# DIO.net
KiCad netlist of a schematic drawn in Altium Designer
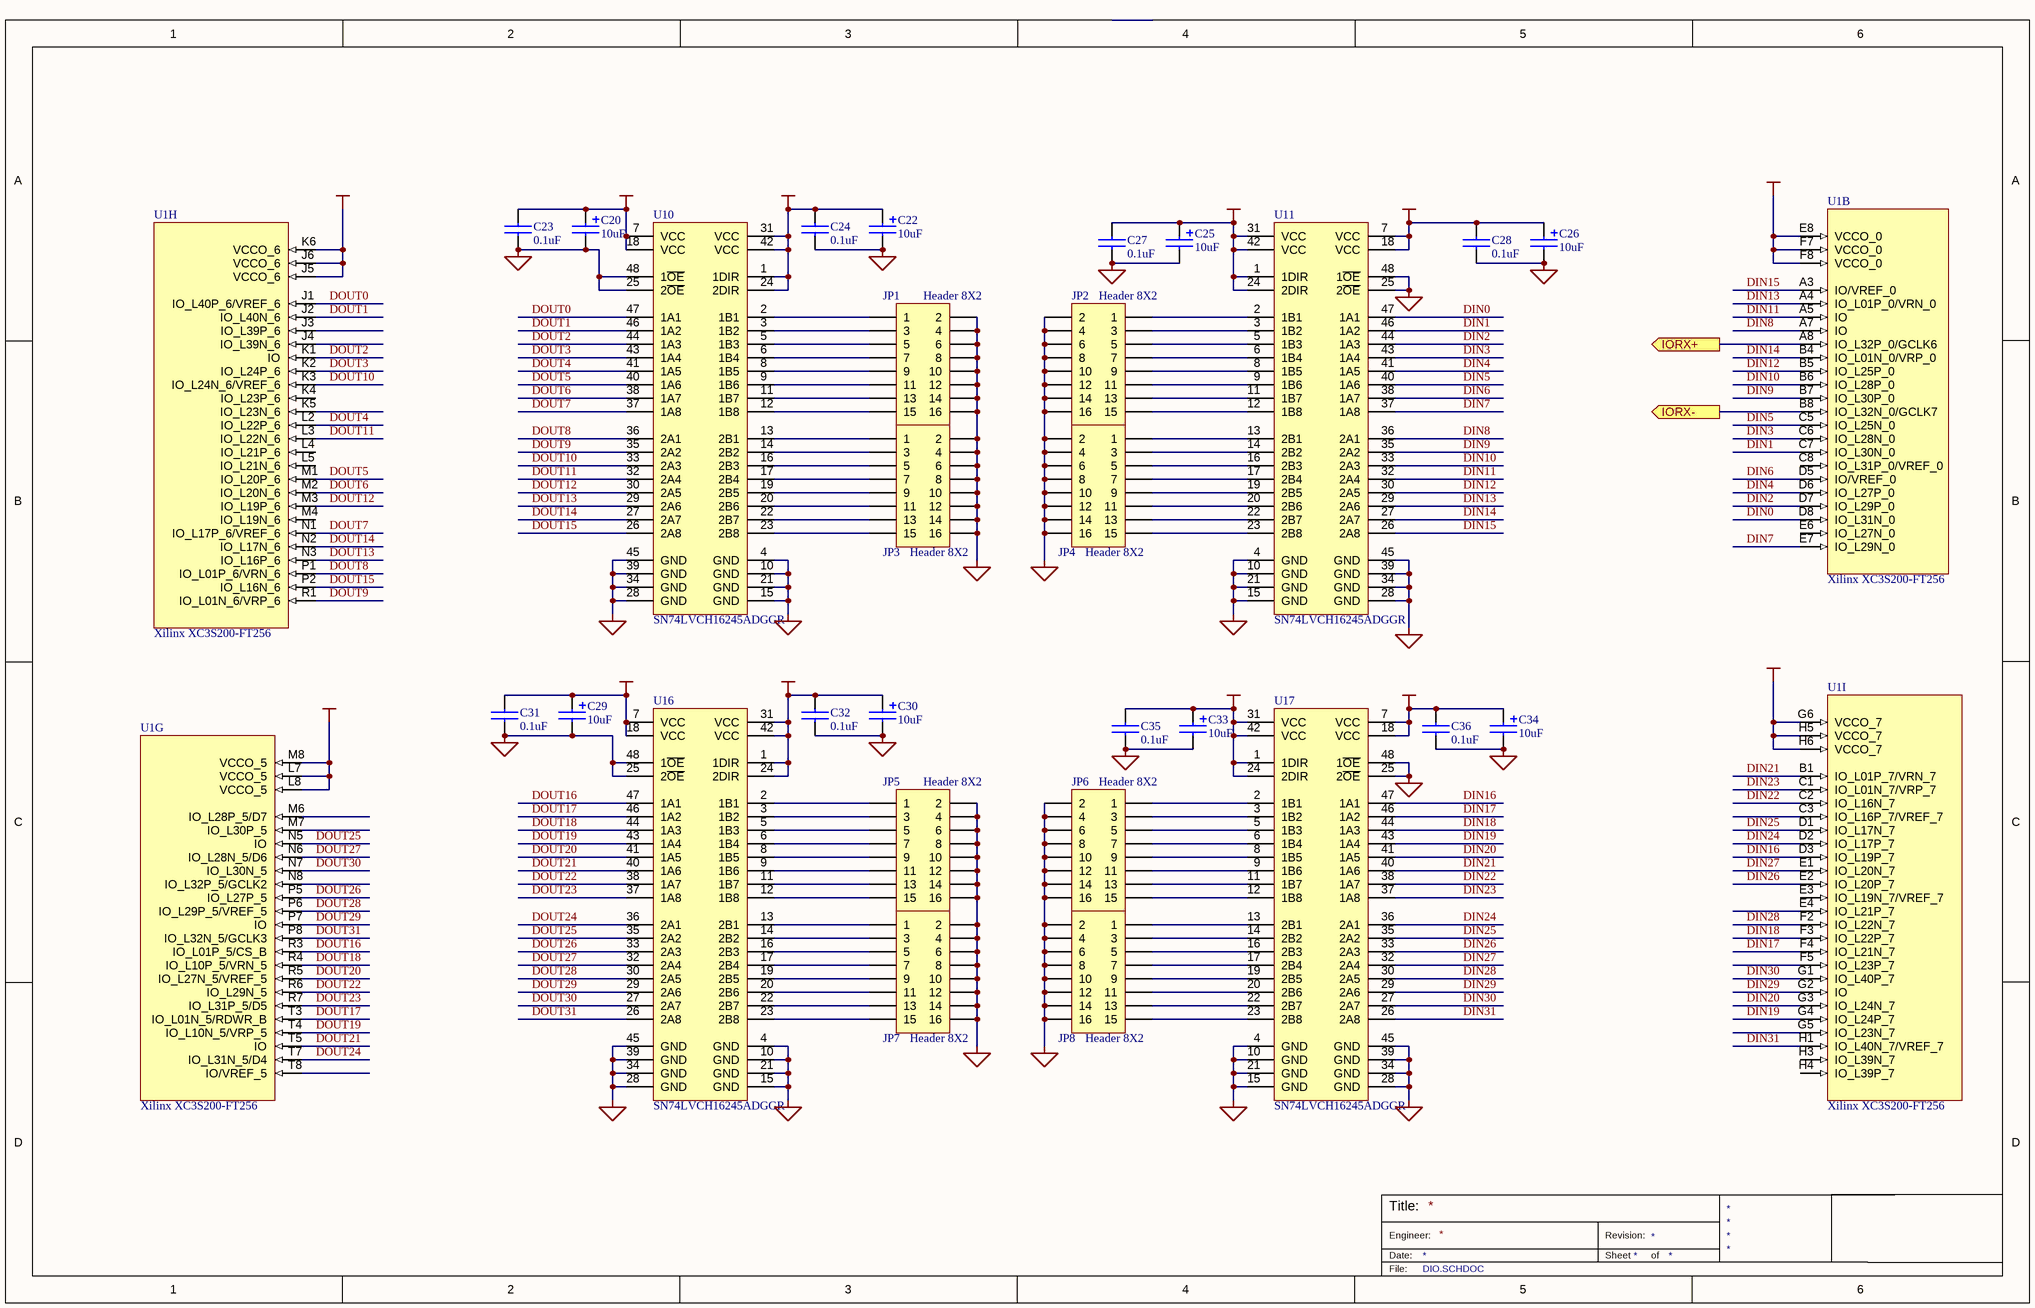
[diagram p0: DIO.SCHDOC]

(export (version "E")
  (design (tool "Eeschema 10.0.6"))
  (components
    (comp (ref "C20")
      (value "10uF")
      (footprint "3216")
      (description "Standard Capacitor")
      (fields (field (name "Comment") "POLCAP"))
      (libsource (lib "parts") (part "POLCAP"))
    )
    (comp (ref "C22")
      (value "10uF")
      (footprint "3216")
      (description "Standard Capacitor")
      (fields (field (name "Comment") "POLCAP"))
      (libsource (lib "parts") (part "POLCAP"))
    )
    (comp (ref "C23")
      (value "0.1uF")
      (footprint "0603")
      (description "Standard Capacitor")
      (fields (field (name "Comment") "CAPACITOR"))
      (libsource (lib "parts") (part "CAPACITOR"))
    )
    (comp (ref "C24")
      (value "0.1uF")
      (footprint "0603")
      (description "Standard Capacitor")
      (fields (field (name "Comment") "CAPACITOR"))
      (libsource (lib "parts") (part "CAPACITOR"))
    )
    (comp (ref "C25")
      (value "10uF")
      (footprint "3216")
      (description "Standard Capacitor")
      (fields (field (name "Comment") "POLCAP"))
      (libsource (lib "parts") (part "POLCAP"))
    )
    (comp (ref "C26")
      (value "10uF")
      (footprint "3216")
      (description "Standard Capacitor")
      (fields (field (name "Comment") "POLCAP"))
      (libsource (lib "parts") (part "POLCAP"))
    )
    (comp (ref "C27")
      (value "0.1uF")
      (footprint "0603")
      (description "Standard Capacitor")
      (fields (field (name "Comment") "CAPACITOR"))
      (libsource (lib "parts") (part "CAPACITOR"))
    )
    (comp (ref "C28")
      (value "0.1uF")
      (footprint "0603")
      (description "Standard Capacitor")
      (fields (field (name "Comment") "CAPACITOR"))
      (libsource (lib "parts") (part "CAPACITOR"))
    )
    (comp (ref "C29")
      (value "10uF")
      (footprint "3216")
      (description "Standard Capacitor")
      (fields (field (name "Comment") "POLCAP"))
      (libsource (lib "parts") (part "POLCAP"))
    )
    (comp (ref "C30")
      (value "10uF")
      (footprint "3216")
      (description "Standard Capacitor")
      (fields (field (name "Comment") "POLCAP"))
      (libsource (lib "parts") (part "POLCAP"))
    )
    (comp (ref "C31")
      (value "0.1uF")
      (footprint "0603")
      (description "Standard Capacitor")
      (fields (field (name "Comment") "CAPACITOR"))
      (libsource (lib "parts") (part "CAPACITOR"))
    )
    (comp (ref "C32")
      (value "0.1uF")
      (footprint "0603")
      (description "Standard Capacitor")
      (fields (field (name "Comment") "CAPACITOR"))
      (libsource (lib "parts") (part "CAPACITOR"))
    )
    (comp (ref "C33")
      (value "10uF")
      (footprint "3216")
      (description "Standard Capacitor")
      (fields (field (name "Comment") "POLCAP"))
      (libsource (lib "parts") (part "POLCAP"))
    )
    (comp (ref "C34")
      (value "10uF")
      (footprint "3216")
      (description "Standard Capacitor")
      (fields (field (name "Comment") "POLCAP"))
      (libsource (lib "parts") (part "POLCAP"))
    )
    (comp (ref "C35")
      (value "0.1uF")
      (footprint "0603")
      (description "Standard Capacitor")
      (fields (field (name "Comment") "CAPACITOR"))
      (libsource (lib "parts") (part "CAPACITOR"))
    )
    (comp (ref "C36")
      (value "0.1uF")
      (footprint "0603")
      (description "Standard Capacitor")
      (fields (field (name "Comment") "CAPACITOR"))
      (libsource (lib "parts") (part "CAPACITOR"))
    )
    (comp (ref "JP1")
      (value "Header 8X2")
      (footprint "HDR2X8")
      (description "Header, 8-Pin, Dual row")
      (fields (field (name "MANUFACTURER") "Generic Components") (field (name "PUBLISHER") "Altium Limited"))
      (libsource (lib "") (part "Header 8X2_1"))
    )
    (comp (ref "JP2")
      (value "Header 8X2")
      (footprint "HDR2X8")
      (description "Header, 8-Pin, Dual row")
      (fields (field (name "MANUFACTURER") "Generic Components") (field (name "PUBLISHER") "Altium Limited"))
      (libsource (lib "Miscellaneous Connectors") (part "Header 8X2"))
    )
    (comp (ref "JP3")
      (value "Header 8X2")
      (footprint "HDR2X8")
      (description "Header, 8-Pin, Dual row")
      (fields (field (name "MANUFACTURER") "Generic Components") (field (name "PUBLISHER") "Altium Limited"))
      (libsource (lib "") (part "Header 8X2_1"))
    )
    (comp (ref "JP4")
      (value "Header 8X2")
      (footprint "HDR2X8")
      (description "Header, 8-Pin, Dual row")
      (fields (field (name "MANUFACTURER") "Generic Components") (field (name "PUBLISHER") "Altium Limited"))
      (libsource (lib "Miscellaneous Connectors") (part "Header 8X2"))
    )
    (comp (ref "JP5")
      (value "Header 8X2")
      (footprint "HDR2X8")
      (description "Header, 8-Pin, Dual row")
      (fields (field (name "MANUFACTURER") "Generic Components") (field (name "PUBLISHER") "Altium Limited"))
      (libsource (lib "") (part "Header 8X2_1"))
    )
    (comp (ref "JP6")
      (value "Header 8X2")
      (footprint "HDR2X8")
      (description "Header, 8-Pin, Dual row")
      (fields (field (name "MANUFACTURER") "Generic Components") (field (name "PUBLISHER") "Altium Limited"))
      (libsource (lib "Miscellaneous Connectors") (part "Header 8X2"))
    )
    (comp (ref "JP7")
      (value "Header 8X2")
      (footprint "HDR2X8")
      (description "Header, 8-Pin, Dual row")
      (fields (field (name "MANUFACTURER") "Generic Components") (field (name "PUBLISHER") "Altium Limited"))
      (libsource (lib "") (part "Header 8X2_1"))
    )
    (comp (ref "JP8")
      (value "Header 8X2")
      (footprint "HDR2X8")
      (description "Header, 8-Pin, Dual row")
      (fields (field (name "MANUFACTURER") "Generic Components") (field (name "PUBLISHER") "Altium Limited"))
      (libsource (lib "Miscellaneous Connectors") (part "Header 8X2"))
    )
    (comp (ref "U1")
      (value "Xilinx XC3S200-FT256")
      (footprint "Xilinx FT256 BGA")
      (description "Xilinx Spartan-3 FPGA")
      (libsource (lib "") (part "XC3S200-FT256_1"))
    )
    (comp (ref "U10")
      (value "SN74LVCH16245ADGGR")
      (footprint "TSSO12x8-G48/X.3")
      (description "16-bit bus transceiver with 3-state outputs")
      (libsource (lib "") (part "SN74LVCH16245ADGGR_1"))
    )
    (comp (ref "U11")
      (value "SN74LVCH16245ADGGR")
      (footprint "TSSO12x8-G48/X.3")
      (description "16-bit bus transceiver with 3-state outputs")
      (libsource (lib "parts") (part "SN74LVCH16245ADGGR"))
    )
    (comp (ref "U16")
      (value "SN74LVCH16245ADGGR")
      (footprint "TSSO12x8-G48/X.3")
      (description "16-bit bus transceiver with 3-state outputs")
      (libsource (lib "") (part "SN74LVCH16245ADGGR_1"))
    )
    (comp (ref "U17")
      (value "SN74LVCH16245ADGGR")
      (footprint "TSSO12x8-G48/X.3")
      (description "16-bit bus transceiver with 3-state outputs")
      (libsource (lib "parts") (part "SN74LVCH16245ADGGR"))
    )
  )
  (nets
    (net (code "1") (name "+2.5VCC") (class "Default")
      (node (ref "C22") (pin "1") (pintype "passive"))
      (node (ref "C24") (pin "1") (pintype "passive"))
      (node (ref "C25") (pin "1") (pintype "passive"))
      (node (ref "C27") (pin "1") (pintype "passive"))
      (node (ref "C30") (pin "1") (pintype "passive"))
      (node (ref "C32") (pin "1") (pintype "passive"))
      (node (ref "C33") (pin "1") (pintype "passive"))
      (node (ref "C35") (pin "1") (pintype "passive"))
      (node (ref "U1") (pin "E8") (pinfunction "VCCO_0_E8") (pintype "input"))
      (node (ref "U1") (pin "F7") (pinfunction "VCCO_0_F7") (pintype "input"))
      (node (ref "U1") (pin "F8") (pinfunction "VCCO_0_F8") (pintype "input"))
      (node (ref "U1") (pin "G6") (pinfunction "VCCO_7_G6") (pintype "input"))
      (node (ref "U1") (pin "H5") (pinfunction "VCCO_7_H5") (pintype "input"))
      (node (ref "U1") (pin "H6") (pinfunction "VCCO_7_H6") (pintype "input"))
      (node (ref "U1") (pin "J5") (pinfunction "VCCO_6_J5") (pintype "input"))
      (node (ref "U1") (pin "J6") (pinfunction "VCCO_6_J6") (pintype "input"))
      (node (ref "U1") (pin "K6") (pinfunction "VCCO_6_K6") (pintype "input"))
      (node (ref "U1") (pin "L7") (pinfunction "VCCO_5_L7") (pintype "input"))
      (node (ref "U1") (pin "L8") (pinfunction "VCCO_5_L8") (pintype "input"))
      (node (ref "U1") (pin "M8") (pinfunction "VCCO_5_M8") (pintype "input"))
      (node (ref "U10") (pin "1") (pinfunction "1DIR_1") (pintype "passive"))
      (node (ref "U10") (pin "24") (pinfunction "2DIR_24") (pintype "passive"))
      (node (ref "U10") (pin "31") (pinfunction "VCC_31") (pintype "power_in"))
      (node (ref "U10") (pin "42") (pinfunction "VCC_42") (pintype "power_in"))
      (node (ref "U11") (pin "1") (pinfunction "1DIR_1") (pintype "passive"))
      (node (ref "U11") (pin "24") (pinfunction "2DIR_24") (pintype "passive"))
      (node (ref "U11") (pin "31") (pinfunction "VCC_31") (pintype "power_in"))
      (node (ref "U11") (pin "42") (pinfunction "VCC_42") (pintype "power_in"))
      (node (ref "U16") (pin "1") (pinfunction "1DIR_1") (pintype "passive"))
      (node (ref "U16") (pin "24") (pinfunction "2DIR_24") (pintype "passive"))
      (node (ref "U16") (pin "31") (pinfunction "VCC_31") (pintype "power_in"))
      (node (ref "U16") (pin "42") (pinfunction "VCC_42") (pintype "power_in"))
      (node (ref "U17") (pin "1") (pinfunction "1DIR_1") (pintype "passive"))
      (node (ref "U17") (pin "24") (pinfunction "2DIR_24") (pintype "passive"))
      (node (ref "U17") (pin "31") (pinfunction "VCC_31") (pintype "power_in"))
      (node (ref "U17") (pin "42") (pinfunction "VCC_42") (pintype "power_in"))
    )
    (net (code "2") (name "+5VCC") (class "Default")
      (node (ref "C20") (pin "1") (pintype "passive"))
      (node (ref "C23") (pin "1") (pintype "passive"))
      (node (ref "C26") (pin "1") (pintype "passive"))
      (node (ref "C28") (pin "1") (pintype "passive"))
      (node (ref "C29") (pin "1") (pintype "passive"))
      (node (ref "C31") (pin "1") (pintype "passive"))
      (node (ref "C34") (pin "1") (pintype "passive"))
      (node (ref "C36") (pin "1") (pintype "passive"))
      (node (ref "U10") (pin "18") (pinfunction "VCC_18") (pintype "power_in"))
      (node (ref "U10") (pin "7") (pinfunction "VCC_7") (pintype "power_in"))
      (node (ref "U11") (pin "18") (pinfunction "VCC_18") (pintype "power_in"))
      (node (ref "U11") (pin "7") (pinfunction "VCC_7") (pintype "power_in"))
      (node (ref "U16") (pin "18") (pinfunction "VCC_18") (pintype "power_in"))
      (node (ref "U16") (pin "7") (pinfunction "VCC_7") (pintype "power_in"))
      (node (ref "U17") (pin "18") (pinfunction "VCC_18") (pintype "power_in"))
      (node (ref "U17") (pin "7") (pinfunction "VCC_7") (pintype "power_in"))
    )
    (net (code "3") (name "/DIN0") (class "Default")
      (node (ref "U1") (pin "D8") (pinfunction "IO_L31N_0_D8") (pintype "input"))
      (node (ref "U11") (pin "47") (pinfunction "1A1_47") (pintype "passive"))
    )
    (net (code "4") (name "/DIN1") (class "Default")
      (node (ref "U1") (pin "C7") (pinfunction "IO_L30N_0_C7") (pintype "input"))
      (node (ref "U11") (pin "46") (pinfunction "1A2_46") (pintype "passive"))
    )
    (net (code "5") (name "/DIN2") (class "Default")
      (node (ref "U1") (pin "D7") (pinfunction "IO_L29P_0_D7") (pintype "input"))
      (node (ref "U11") (pin "44") (pinfunction "1A3_44") (pintype "passive"))
    )
    (net (code "6") (name "/DIN3") (class "Default")
      (node (ref "U1") (pin "C6") (pinfunction "IO_L28N_0_C6") (pintype "input"))
      (node (ref "U11") (pin "43") (pinfunction "1A4_43") (pintype "passive"))
    )
    (net (code "7") (name "/DIN4") (class "Default")
      (node (ref "U1") (pin "D6") (pinfunction "IO_L27P_0_D6") (pintype "input"))
      (node (ref "U11") (pin "41") (pinfunction "1A5_41") (pintype "passive"))
    )
    (net (code "8") (name "/DIN5") (class "Default")
      (node (ref "U1") (pin "C5") (pinfunction "IO_L25N_0_C5") (pintype "input"))
      (node (ref "U11") (pin "40") (pinfunction "1A6_40") (pintype "passive"))
    )
    (net (code "9") (name "/DIN6") (class "Default")
      (node (ref "U1") (pin "D5") (pinfunction "IO/VREF_0_D5") (pintype "input"))
      (node (ref "U11") (pin "38") (pinfunction "1A7_38") (pintype "passive"))
    )
    (net (code "10") (name "/DIN7") (class "Default")
      (node (ref "U1") (pin "E7") (pinfunction "IO_L29N_0_E7") (pintype "input"))
      (node (ref "U11") (pin "37") (pinfunction "1A8_37") (pintype "passive"))
    )
    (net (code "11") (name "/DIN8") (class "Default")
      (node (ref "U1") (pin "A7") (pinfunction "IO_A7") (pintype "input"))
      (node (ref "U11") (pin "36") (pinfunction "2A1_36") (pintype "passive"))
    )
    (net (code "12") (name "/DIN9") (class "Default")
      (node (ref "U1") (pin "B7") (pinfunction "IO_L30P_0_B7") (pintype "input"))
      (node (ref "U11") (pin "35") (pinfunction "2A2_35") (pintype "passive"))
    )
    (net (code "13") (name "/DIN10") (class "Default")
      (node (ref "U1") (pin "B6") (pinfunction "IO_L28P_0_B6") (pintype "input"))
      (node (ref "U11") (pin "33") (pinfunction "2A3_33") (pintype "passive"))
    )
    (net (code "14") (name "/DIN11") (class "Default")
      (node (ref "U1") (pin "A5") (pinfunction "IO_A5") (pintype "input"))
      (node (ref "U11") (pin "32") (pinfunction "2A4_32") (pintype "passive"))
    )
    (net (code "15") (name "/DIN12") (class "Default")
      (node (ref "U1") (pin "B5") (pinfunction "IO_L25P_0_B5") (pintype "input"))
      (node (ref "U11") (pin "30") (pinfunction "2A5_30") (pintype "passive"))
    )
    (net (code "16") (name "/DIN13") (class "Default")
      (node (ref "U1") (pin "A4") (pinfunction "IO_L01P_0/VRN_0_A4") (pintype "input"))
      (node (ref "U11") (pin "29") (pinfunction "2A6_29") (pintype "passive"))
    )
    (net (code "17") (name "/DIN14") (class "Default")
      (node (ref "U1") (pin "B4") (pinfunction "IO_L01N_0/VRP_0_B4") (pintype "input"))
      (node (ref "U11") (pin "27") (pinfunction "2A7_27") (pintype "passive"))
    )
    (net (code "18") (name "/DIN15") (class "Default")
      (node (ref "U1") (pin "A3") (pinfunction "IO/VREF_0_A3") (pintype "input"))
      (node (ref "U11") (pin "26") (pinfunction "2A8_26") (pintype "passive"))
    )
    (net (code "19") (name "/DIN16") (class "Default")
      (node (ref "U1") (pin "D3") (pinfunction "IO_L19P_7_D3") (pintype "input"))
      (node (ref "U17") (pin "47") (pinfunction "1A1_47") (pintype "passive"))
    )
    (net (code "20") (name "/DIN17") (class "Default")
      (node (ref "U1") (pin "F4") (pinfunction "IO_L21N_7_F4") (pintype "input"))
      (node (ref "U17") (pin "46") (pinfunction "1A2_46") (pintype "passive"))
    )
    (net (code "21") (name "/DIN18") (class "Default")
      (node (ref "U1") (pin "F3") (pinfunction "IO_L22P_7_F3") (pintype "input"))
      (node (ref "U17") (pin "44") (pinfunction "1A3_44") (pintype "passive"))
    )
    (net (code "22") (name "/DIN19") (class "Default")
      (node (ref "U1") (pin "G4") (pinfunction "IO_L24P_7_G4") (pintype "input"))
      (node (ref "U17") (pin "43") (pinfunction "1A4_43") (pintype "passive"))
    )
    (net (code "23") (name "/DIN20") (class "Default")
      (node (ref "U1") (pin "G3") (pinfunction "IO_L24N_7_G3") (pintype "input"))
      (node (ref "U17") (pin "41") (pinfunction "1A5_41") (pintype "passive"))
    )
    (net (code "24") (name "/DIN21") (class "Default")
      (node (ref "U1") (pin "B1") (pinfunction "IO_L01P_7/VRN_7_B1") (pintype "input"))
      (node (ref "U17") (pin "40") (pinfunction "1A6_40") (pintype "passive"))
    )
    (net (code "25") (name "/DIN22") (class "Default")
      (node (ref "U1") (pin "C2") (pinfunction "IO_L16N_7_C2") (pintype "input"))
      (node (ref "U17") (pin "38") (pinfunction "1A7_38") (pintype "passive"))
    )
    (net (code "26") (name "/DIN23") (class "Default")
      (node (ref "U1") (pin "C1") (pinfunction "IO_L01N_7/VRP_7_C1") (pintype "input"))
      (node (ref "U17") (pin "37") (pinfunction "1A8_37") (pintype "passive"))
    )
    (net (code "27") (name "/DIN24") (class "Default")
      (node (ref "U1") (pin "D2") (pinfunction "IO_L17P_7_D2") (pintype "input"))
      (node (ref "U17") (pin "36") (pinfunction "2A1_36") (pintype "passive"))
    )
    (net (code "28") (name "/DIN25") (class "Default")
      (node (ref "U1") (pin "D1") (pinfunction "IO_L17N_7_D1") (pintype "input"))
      (node (ref "U17") (pin "35") (pinfunction "2A2_35") (pintype "passive"))
    )
    (net (code "29") (name "/DIN26") (class "Default")
      (node (ref "U1") (pin "E2") (pinfunction "IO_L20P_7_E2") (pintype "input"))
      (node (ref "U17") (pin "33") (pinfunction "2A3_33") (pintype "passive"))
    )
    (net (code "30") (name "/DIN27") (class "Default")
      (node (ref "U1") (pin "E1") (pinfunction "IO_L20N_7_E1") (pintype "input"))
      (node (ref "U17") (pin "32") (pinfunction "2A4_32") (pintype "passive"))
    )
    (net (code "31") (name "/DIN28") (class "Default")
      (node (ref "U1") (pin "F2") (pinfunction "IO_L22N_7_F2") (pintype "input"))
      (node (ref "U17") (pin "30") (pinfunction "2A5_30") (pintype "passive"))
    )
    (net (code "32") (name "/DIN29") (class "Default")
      (node (ref "U1") (pin "G2") (pinfunction "IO_G2") (pintype "input"))
      (node (ref "U17") (pin "29") (pinfunction "2A6_29") (pintype "passive"))
    )
    (net (code "33") (name "/DIN30") (class "Default")
      (node (ref "U1") (pin "G1") (pinfunction "IO_L40P_7_G1") (pintype "input"))
      (node (ref "U17") (pin "27") (pinfunction "2A7_27") (pintype "passive"))
    )
    (net (code "34") (name "/DIN31") (class "Default")
      (node (ref "U1") (pin "H1") (pinfunction "IO_L40N_7/VREF_7_H1") (pintype "input"))
      (node (ref "U17") (pin "26") (pinfunction "2A8_26") (pintype "passive"))
    )
    (net (code "35") (name "/DOUT0") (class "Default")
      (node (ref "U1") (pin "J1") (pinfunction "IO_L40P_6/VREF_6_J1") (pintype "input"))
      (node (ref "U10") (pin "47") (pinfunction "1A1_47") (pintype "passive"))
    )
    (net (code "36") (name "/DOUT1") (class "Default")
      (node (ref "U1") (pin "J2") (pinfunction "IO_L40N_6_J2") (pintype "input"))
      (node (ref "U10") (pin "46") (pinfunction "1A2_46") (pintype "passive"))
    )
    (net (code "37") (name "/DOUT2") (class "Default")
      (node (ref "U1") (pin "K1") (pinfunction "IO_K1") (pintype "input"))
      (node (ref "U10") (pin "44") (pinfunction "1A3_44") (pintype "passive"))
    )
    (net (code "38") (name "/DOUT3") (class "Default")
      (node (ref "U1") (pin "K2") (pinfunction "IO_L24P_6_K2") (pintype "input"))
      (node (ref "U10") (pin "43") (pinfunction "1A4_43") (pintype "passive"))
    )
    (net (code "39") (name "/DOUT4") (class "Default")
      (node (ref "U1") (pin "L2") (pinfunction "IO_L22P_6_L2") (pintype "input"))
      (node (ref "U10") (pin "41") (pinfunction "1A5_41") (pintype "passive"))
    )
    (net (code "40") (name "/DOUT5") (class "Default")
      (node (ref "U1") (pin "M1") (pinfunction "IO_L20P_6_M1") (pintype "input"))
      (node (ref "U10") (pin "40") (pinfunction "1A6_40") (pintype "passive"))
    )
    (net (code "41") (name "/DOUT6") (class "Default")
      (node (ref "U1") (pin "M2") (pinfunction "IO_L20N_6_M2") (pintype "input"))
      (node (ref "U10") (pin "38") (pinfunction "1A7_38") (pintype "passive"))
    )
    (net (code "42") (name "/DOUT7") (class "Default")
      (node (ref "U1") (pin "N1") (pinfunction "IO_L17P_6/VREF_6_N1") (pintype "input"))
      (node (ref "U10") (pin "37") (pinfunction "1A8_37") (pintype "passive"))
    )
    (net (code "43") (name "/DOUT8") (class "Default")
      (node (ref "U1") (pin "P1") (pinfunction "IO_L01P_6/VRN_6_P1") (pintype "input"))
      (node (ref "U10") (pin "36") (pinfunction "2A1_36") (pintype "passive"))
    )
    (net (code "44") (name "/DOUT9") (class "Default")
      (node (ref "U1") (pin "R1") (pinfunction "IO_L01N_6/VRP_6_R1") (pintype "input"))
      (node (ref "U10") (pin "35") (pinfunction "2A2_35") (pintype "passive"))
    )
    (net (code "45") (name "/DOUT10") (class "Default")
      (node (ref "U1") (pin "K3") (pinfunction "IO_L24N_6/VREF_6_K3") (pintype "input"))
      (node (ref "U10") (pin "33") (pinfunction "2A3_33") (pintype "passive"))
    )
    (net (code "46") (name "/DOUT11") (class "Default")
      (node (ref "U1") (pin "L3") (pinfunction "IO_L22N_6_L3") (pintype "input"))
      (node (ref "U10") (pin "32") (pinfunction "2A4_32") (pintype "passive"))
    )
    (net (code "47") (name "/DOUT12") (class "Default")
      (node (ref "U1") (pin "M3") (pinfunction "IO_L19P_6_M3") (pintype "input"))
      (node (ref "U10") (pin "30") (pinfunction "2A5_30") (pintype "passive"))
    )
    (net (code "48") (name "/DOUT13") (class "Default")
      (node (ref "U1") (pin "N3") (pinfunction "IO_L16P_6_N3") (pintype "input"))
      (node (ref "U10") (pin "29") (pinfunction "2A6_29") (pintype "passive"))
    )
    (net (code "49") (name "/DOUT14") (class "Default")
      (node (ref "U1") (pin "N2") (pinfunction "IO_L17N_6_N2") (pintype "input"))
      (node (ref "U10") (pin "27") (pinfunction "2A7_27") (pintype "passive"))
    )
    (net (code "50") (name "/DOUT15") (class "Default")
      (node (ref "U1") (pin "P2") (pinfunction "IO_L16N_6_P2") (pintype "input"))
      (node (ref "U10") (pin "26") (pinfunction "2A8_26") (pintype "passive"))
    )
    (net (code "51") (name "/DOUT16") (class "Default")
      (node (ref "U1") (pin "R3") (pinfunction "IO_L01P_5/CS_B_R3") (pintype "input"))
      (node (ref "U16") (pin "47") (pinfunction "1A1_47") (pintype "passive"))
    )
    (net (code "52") (name "/DOUT17") (class "Default")
      (node (ref "U1") (pin "T3") (pinfunction "IO_L01N_5/RDWR_B_T3") (pintype "input"))
      (node (ref "U16") (pin "46") (pinfunction "1A2_46") (pintype "passive"))
    )
    (net (code "53") (name "/DOUT18") (class "Default")
      (node (ref "U1") (pin "R4") (pinfunction "IO_L10P_5/VRN_5_R4") (pintype "input"))
      (node (ref "U16") (pin "44") (pinfunction "1A3_44") (pintype "passive"))
    )
    (net (code "54") (name "/DOUT19") (class "Default")
      (node (ref "U1") (pin "T4") (pinfunction "IO_L10N_5/VRP_5_T4") (pintype "input"))
      (node (ref "U16") (pin "43") (pinfunction "1A4_43") (pintype "passive"))
    )
    (net (code "55") (name "/DOUT20") (class "Default")
      (node (ref "U1") (pin "R5") (pinfunction "IO_L27N_5/VREF_5_R5") (pintype "input"))
      (node (ref "U16") (pin "41") (pinfunction "1A5_41") (pintype "passive"))
    )
    (net (code "56") (name "/DOUT21") (class "Default")
      (node (ref "U1") (pin "T5") (pinfunction "IO_T5") (pintype "input"))
      (node (ref "U16") (pin "40") (pinfunction "1A6_40") (pintype "passive"))
    )
    (net (code "57") (name "/DOUT22") (class "Default")
      (node (ref "U1") (pin "R6") (pinfunction "IO_L29N_5_R6") (pintype "input"))
      (node (ref "U16") (pin "38") (pinfunction "1A7_38") (pintype "passive"))
    )
    (net (code "58") (name "/DOUT23") (class "Default")
      (node (ref "U1") (pin "R7") (pinfunction "IO_L31P_5/D5_R7") (pintype "input"))
      (node (ref "U16") (pin "37") (pinfunction "1A8_37") (pintype "passive"))
    )
    (net (code "59") (name "/DOUT24") (class "Default")
      (node (ref "U1") (pin "T7") (pinfunction "IO_L31N_5/D4_T7") (pintype "input"))
      (node (ref "U16") (pin "36") (pinfunction "2A1_36") (pintype "passive"))
    )
    (net (code "60") (name "/DOUT25") (class "Default")
      (node (ref "U1") (pin "N5") (pinfunction "IO_N5") (pintype "input"))
      (node (ref "U16") (pin "35") (pinfunction "2A2_35") (pintype "passive"))
    )
    (net (code "61") (name "/DOUT26") (class "Default")
      (node (ref "U1") (pin "P5") (pinfunction "IO_L27P_5_P5") (pintype "input"))
      (node (ref "U16") (pin "33") (pinfunction "2A3_33") (pintype "passive"))
    )
    (net (code "62") (name "/DOUT27") (class "Default")
      (node (ref "U1") (pin "N6") (pinfunction "IO_L28N_5/D6_N6") (pintype "input"))
      (node (ref "U16") (pin "32") (pinfunction "2A4_32") (pintype "passive"))
    )
    (net (code "63") (name "/DOUT28") (class "Default")
      (node (ref "U1") (pin "P6") (pinfunction "IO_L29P_5/VREF_5_P6") (pintype "input"))
      (node (ref "U16") (pin "30") (pinfunction "2A5_30") (pintype "passive"))
    )
    (net (code "64") (name "/DOUT29") (class "Default")
      (node (ref "U1") (pin "P7") (pinfunction "IO_P7") (pintype "input"))
      (node (ref "U16") (pin "29") (pinfunction "2A6_29") (pintype "passive"))
    )
    (net (code "65") (name "/DOUT30") (class "Default")
      (node (ref "U1") (pin "N7") (pinfunction "IO_L30N_5_N7") (pintype "input"))
      (node (ref "U16") (pin "27") (pinfunction "2A7_27") (pintype "passive"))
    )
    (net (code "66") (name "/DOUT31") (class "Default")
      (node (ref "U1") (pin "P8") (pinfunction "IO_L32N_5/GCLK3_P8") (pintype "input"))
      (node (ref "U16") (pin "26") (pinfunction "2A8_26") (pintype "passive"))
    )
    (net (code "67") (name "/IORX+") (class "Default")
      (node (ref "U1") (pin "A8") (pinfunction "IO_L32P_0/GCLK6_A8") (pintype "input"))
    )
    (net (code "68") (name "/IORX-") (class "Default")
      (node (ref "U1") (pin "B8") (pinfunction "IO_L32N_0/GCLK7_B8") (pintype "input"))
    )
    (net (code "69") (name "GND") (class "Default")
      (node (ref "C20") (pin "2") (pintype "passive"))
      (node (ref "C22") (pin "2") (pintype "passive"))
      (node (ref "C23") (pin "2") (pintype "passive"))
      (node (ref "C24") (pin "2") (pintype "passive"))
      (node (ref "C25") (pin "2") (pintype "passive"))
      (node (ref "C26") (pin "2") (pintype "passive"))
      (node (ref "C27") (pin "2") (pintype "passive"))
      (node (ref "C28") (pin "2") (pintype "passive"))
      (node (ref "C29") (pin "2") (pintype "passive"))
      (node (ref "C30") (pin "2") (pintype "passive"))
      (node (ref "C31") (pin "2") (pintype "passive"))
      (node (ref "C32") (pin "2") (pintype "passive"))
      (node (ref "C33") (pin "2") (pintype "passive"))
      (node (ref "C34") (pin "2") (pintype "passive"))
      (node (ref "C35") (pin "2") (pintype "passive"))
      (node (ref "C36") (pin "2") (pintype "passive"))
      (node (ref "JP1") (pin "10") (pinfunction "10_10") (pintype "passive"))
      (node (ref "JP1") (pin "12") (pinfunction "12_12") (pintype "passive"))
      (node (ref "JP1") (pin "14") (pinfunction "14_14") (pintype "passive"))
      (node (ref "JP1") (pin "16") (pinfunction "16_16") (pintype "passive"))
      (node (ref "JP1") (pin "2") (pinfunction "2_2") (pintype "passive"))
      (node (ref "JP1") (pin "4") (pinfunction "4_4") (pintype "passive"))
      (node (ref "JP1") (pin "6") (pinfunction "6_6") (pintype "passive"))
      (node (ref "JP1") (pin "8") (pinfunction "8_8") (pintype "passive"))
      (node (ref "JP2") (pin "10") (pinfunction "10_10") (pintype "passive"))
      (node (ref "JP2") (pin "12") (pinfunction "12_12") (pintype "passive"))
      (node (ref "JP2") (pin "14") (pinfunction "14_14") (pintype "passive"))
      (node (ref "JP2") (pin "16") (pinfunction "16_16") (pintype "passive"))
      (node (ref "JP2") (pin "2") (pinfunction "2_2") (pintype "passive"))
      (node (ref "JP2") (pin "4") (pinfunction "4_4") (pintype "passive"))
      (node (ref "JP2") (pin "6") (pinfunction "6_6") (pintype "passive"))
      (node (ref "JP2") (pin "8") (pinfunction "8_8") (pintype "passive"))
      (node (ref "JP3") (pin "10") (pinfunction "10_10") (pintype "passive"))
      (node (ref "JP3") (pin "12") (pinfunction "12_12") (pintype "passive"))
      (node (ref "JP3") (pin "14") (pinfunction "14_14") (pintype "passive"))
      (node (ref "JP3") (pin "16") (pinfunction "16_16") (pintype "passive"))
      (node (ref "JP3") (pin "2") (pinfunction "2_2") (pintype "passive"))
      (node (ref "JP3") (pin "4") (pinfunction "4_4") (pintype "passive"))
      (node (ref "JP3") (pin "6") (pinfunction "6_6") (pintype "passive"))
      (node (ref "JP3") (pin "8") (pinfunction "8_8") (pintype "passive"))
      (node (ref "JP4") (pin "10") (pinfunction "10_10") (pintype "passive"))
      (node (ref "JP4") (pin "12") (pinfunction "12_12") (pintype "passive"))
      (node (ref "JP4") (pin "14") (pinfunction "14_14") (pintype "passive"))
      (node (ref "JP4") (pin "16") (pinfunction "16_16") (pintype "passive"))
      (node (ref "JP4") (pin "2") (pinfunction "2_2") (pintype "passive"))
      (node (ref "JP4") (pin "4") (pinfunction "4_4") (pintype "passive"))
      (node (ref "JP4") (pin "6") (pinfunction "6_6") (pintype "passive"))
      (node (ref "JP4") (pin "8") (pinfunction "8_8") (pintype "passive"))
      (node (ref "JP5") (pin "10") (pinfunction "10_10") (pintype "passive"))
      (node (ref "JP5") (pin "12") (pinfunction "12_12") (pintype "passive"))
      (node (ref "JP5") (pin "14") (pinfunction "14_14") (pintype "passive"))
      (node (ref "JP5") (pin "16") (pinfunction "16_16") (pintype "passive"))
      (node (ref "JP5") (pin "2") (pinfunction "2_2") (pintype "passive"))
      (node (ref "JP5") (pin "4") (pinfunction "4_4") (pintype "passive"))
      (node (ref "JP5") (pin "6") (pinfunction "6_6") (pintype "passive"))
      (node (ref "JP5") (pin "8") (pinfunction "8_8") (pintype "passive"))
      (node (ref "JP6") (pin "10") (pinfunction "10_10") (pintype "passive"))
      (node (ref "JP6") (pin "12") (pinfunction "12_12") (pintype "passive"))
      (node (ref "JP6") (pin "14") (pinfunction "14_14") (pintype "passive"))
      (node (ref "JP6") (pin "16") (pinfunction "16_16") (pintype "passive"))
      (node (ref "JP6") (pin "2") (pinfunction "2_2") (pintype "passive"))
      (node (ref "JP6") (pin "4") (pinfunction "4_4") (pintype "passive"))
      (node (ref "JP6") (pin "6") (pinfunction "6_6") (pintype "passive"))
      (node (ref "JP6") (pin "8") (pinfunction "8_8") (pintype "passive"))
      (node (ref "JP7") (pin "10") (pinfunction "10_10") (pintype "passive"))
      (node (ref "JP7") (pin "12") (pinfunction "12_12") (pintype "passive"))
      (node (ref "JP7") (pin "14") (pinfunction "14_14") (pintype "passive"))
      (node (ref "JP7") (pin "16") (pinfunction "16_16") (pintype "passive"))
      (node (ref "JP7") (pin "2") (pinfunction "2_2") (pintype "passive"))
      (node (ref "JP7") (pin "4") (pinfunction "4_4") (pintype "passive"))
      (node (ref "JP7") (pin "6") (pinfunction "6_6") (pintype "passive"))
      (node (ref "JP7") (pin "8") (pinfunction "8_8") (pintype "passive"))
      (node (ref "JP8") (pin "10") (pinfunction "10_10") (pintype "passive"))
      (node (ref "JP8") (pin "12") (pinfunction "12_12") (pintype "passive"))
      (node (ref "JP8") (pin "14") (pinfunction "14_14") (pintype "passive"))
      (node (ref "JP8") (pin "16") (pinfunction "16_16") (pintype "passive"))
      (node (ref "JP8") (pin "2") (pinfunction "2_2") (pintype "passive"))
      (node (ref "JP8") (pin "4") (pinfunction "4_4") (pintype "passive"))
      (node (ref "JP8") (pin "6") (pinfunction "6_6") (pintype "passive"))
      (node (ref "JP8") (pin "8") (pinfunction "8_8") (pintype "passive"))
      (node (ref "U10") (pin "10") (pinfunction "GND_10") (pintype "power_in"))
      (node (ref "U10") (pin "15") (pinfunction "GND_15") (pintype "power_in"))
      (node (ref "U10") (pin "21") (pinfunction "GND_21") (pintype "power_in"))
      (node (ref "U10") (pin "25") (pinfunction "2~{OE}_25") (pintype "passive"))
      (node (ref "U10") (pin "28") (pinfunction "GND_28") (pintype "power_in"))
      (node (ref "U10") (pin "34") (pinfunction "GND_34") (pintype "power_in"))
      (node (ref "U10") (pin "39") (pinfunction "GND_39") (pintype "power_in"))
      (node (ref "U10") (pin "4") (pinfunction "GND_4") (pintype "power_in"))
      (node (ref "U10") (pin "45") (pinfunction "GND_45") (pintype "power_in"))
      (node (ref "U10") (pin "48") (pinfunction "1~{OE}_48") (pintype "passive"))
      (node (ref "U11") (pin "10") (pinfunction "GND_10") (pintype "power_in"))
      (node (ref "U11") (pin "15") (pinfunction "GND_15") (pintype "power_in"))
      (node (ref "U11") (pin "21") (pinfunction "GND_21") (pintype "power_in"))
      (node (ref "U11") (pin "25") (pinfunction "2~{OE}_25") (pintype "passive"))
      (node (ref "U11") (pin "28") (pinfunction "GND_28") (pintype "power_in"))
      (node (ref "U11") (pin "34") (pinfunction "GND_34") (pintype "power_in"))
      (node (ref "U11") (pin "39") (pinfunction "GND_39") (pintype "power_in"))
      (node (ref "U11") (pin "4") (pinfunction "GND_4") (pintype "power_in"))
      (node (ref "U11") (pin "45") (pinfunction "GND_45") (pintype "power_in"))
      (node (ref "U11") (pin "48") (pinfunction "1~{OE}_48") (pintype "passive"))
      (node (ref "U16") (pin "10") (pinfunction "GND_10") (pintype "power_in"))
      (node (ref "U16") (pin "15") (pinfunction "GND_15") (pintype "power_in"))
      (node (ref "U16") (pin "21") (pinfunction "GND_21") (pintype "power_in"))
      (node (ref "U16") (pin "25") (pinfunction "2~{OE}_25") (pintype "passive"))
      (node (ref "U16") (pin "28") (pinfunction "GND_28") (pintype "power_in"))
      (node (ref "U16") (pin "34") (pinfunction "GND_34") (pintype "power_in"))
      (node (ref "U16") (pin "39") (pinfunction "GND_39") (pintype "power_in"))
      (node (ref "U16") (pin "4") (pinfunction "GND_4") (pintype "power_in"))
      (node (ref "U16") (pin "45") (pinfunction "GND_45") (pintype "power_in"))
      (node (ref "U16") (pin "48") (pinfunction "1~{OE}_48") (pintype "passive"))
      (node (ref "U17") (pin "10") (pinfunction "GND_10") (pintype "power_in"))
      (node (ref "U17") (pin "15") (pinfunction "GND_15") (pintype "power_in"))
      (node (ref "U17") (pin "21") (pinfunction "GND_21") (pintype "power_in"))
      (node (ref "U17") (pin "25") (pinfunction "2~{OE}_25") (pintype "passive"))
      (node (ref "U17") (pin "28") (pinfunction "GND_28") (pintype "power_in"))
      (node (ref "U17") (pin "34") (pinfunction "GND_34") (pintype "power_in"))
      (node (ref "U17") (pin "39") (pinfunction "GND_39") (pintype "power_in"))
      (node (ref "U17") (pin "4") (pinfunction "GND_4") (pintype "power_in"))
      (node (ref "U17") (pin "45") (pinfunction "GND_45") (pintype "power_in"))
      (node (ref "U17") (pin "48") (pinfunction "1~{OE}_48") (pintype "passive"))
    )
    (net (code "70") (name "Net-(U10-1B1)") (class "Default")
      (node (ref "JP1") (pin "1") (pinfunction "1_1") (pintype "passive"))
      (node (ref "U10") (pin "2") (pinfunction "1B1_2") (pintype "passive"))
    )
    (net (code "71") (name "Net-(U10-1B2)") (class "Default")
      (node (ref "JP1") (pin "3") (pinfunction "3_3") (pintype "passive"))
      (node (ref "U10") (pin "3") (pinfunction "1B2_3") (pintype "passive"))
    )
    (net (code "72") (name "Net-(U10-1B3)") (class "Default")
      (node (ref "JP1") (pin "5") (pinfunction "5_5") (pintype "passive"))
      (node (ref "U10") (pin "5") (pinfunction "1B3_5") (pintype "passive"))
    )
    (net (code "73") (name "Net-(U10-1B4)") (class "Default")
      (node (ref "JP1") (pin "7") (pinfunction "7_7") (pintype "passive"))
      (node (ref "U10") (pin "6") (pinfunction "1B4_6") (pintype "passive"))
    )
    (net (code "74") (name "Net-(U10-1B5)") (class "Default")
      (node (ref "JP1") (pin "9") (pinfunction "9_9") (pintype "passive"))
      (node (ref "U10") (pin "8") (pinfunction "1B5_8") (pintype "passive"))
    )
    (net (code "75") (name "Net-(U10-1B6)") (class "Default")
      (node (ref "JP1") (pin "11") (pinfunction "11_11") (pintype "passive"))
      (node (ref "U10") (pin "9") (pinfunction "1B6_9") (pintype "passive"))
    )
    (net (code "76") (name "Net-(U10-1B7)") (class "Default")
      (node (ref "JP1") (pin "13") (pinfunction "13_13") (pintype "passive"))
      (node (ref "U10") (pin "11") (pinfunction "1B7_11") (pintype "passive"))
    )
    (net (code "77") (name "Net-(U10-1B8)") (class "Default")
      (node (ref "JP1") (pin "15") (pinfunction "15_15") (pintype "passive"))
      (node (ref "U10") (pin "12") (pinfunction "1B8_12") (pintype "passive"))
    )
    (net (code "78") (name "Net-(U10-2B1)") (class "Default")
      (node (ref "JP3") (pin "1") (pinfunction "1_1") (pintype "passive"))
      (node (ref "U10") (pin "13") (pinfunction "2B1_13") (pintype "passive"))
    )
    (net (code "79") (name "Net-(U10-2B2)") (class "Default")
      (node (ref "JP3") (pin "3") (pinfunction "3_3") (pintype "passive"))
      (node (ref "U10") (pin "14") (pinfunction "2B2_14") (pintype "passive"))
    )
    (net (code "80") (name "Net-(U10-2B3)") (class "Default")
      (node (ref "JP3") (pin "5") (pinfunction "5_5") (pintype "passive"))
      (node (ref "U10") (pin "16") (pinfunction "2B3_16") (pintype "passive"))
    )
    (net (code "81") (name "Net-(U10-2B4)") (class "Default")
      (node (ref "JP3") (pin "7") (pinfunction "7_7") (pintype "passive"))
      (node (ref "U10") (pin "17") (pinfunction "2B4_17") (pintype "passive"))
    )
    (net (code "82") (name "Net-(U10-2B5)") (class "Default")
      (node (ref "JP3") (pin "9") (pinfunction "9_9") (pintype "passive"))
      (node (ref "U10") (pin "19") (pinfunction "2B5_19") (pintype "passive"))
    )
    (net (code "83") (name "Net-(U10-2B6)") (class "Default")
      (node (ref "JP3") (pin "11") (pinfunction "11_11") (pintype "passive"))
      (node (ref "U10") (pin "20") (pinfunction "2B6_20") (pintype "passive"))
    )
    (net (code "84") (name "Net-(U10-2B7)") (class "Default")
      (node (ref "JP3") (pin "13") (pinfunction "13_13") (pintype "passive"))
      (node (ref "U10") (pin "22") (pinfunction "2B7_22") (pintype "passive"))
    )
    (net (code "85") (name "Net-(U10-2B8)") (class "Default")
      (node (ref "JP3") (pin "15") (pinfunction "15_15") (pintype "passive"))
      (node (ref "U10") (pin "23") (pinfunction "2B8_23") (pintype "passive"))
    )
    (net (code "86") (name "Net-(U11-1B1)") (class "Default")
      (node (ref "JP2") (pin "1") (pinfunction "1_1") (pintype "passive"))
      (node (ref "U11") (pin "2") (pinfunction "1B1_2") (pintype "passive"))
    )
    (net (code "87") (name "Net-(U11-1B2)") (class "Default")
      (node (ref "JP2") (pin "3") (pinfunction "3_3") (pintype "passive"))
      (node (ref "U11") (pin "3") (pinfunction "1B2_3") (pintype "passive"))
    )
    (net (code "88") (name "Net-(U11-1B3)") (class "Default")
      (node (ref "JP2") (pin "5") (pinfunction "5_5") (pintype "passive"))
      (node (ref "U11") (pin "5") (pinfunction "1B3_5") (pintype "passive"))
    )
    (net (code "89") (name "Net-(U11-1B4)") (class "Default")
      (node (ref "JP2") (pin "7") (pinfunction "7_7") (pintype "passive"))
      (node (ref "U11") (pin "6") (pinfunction "1B4_6") (pintype "passive"))
    )
    (net (code "90") (name "Net-(U11-1B5)") (class "Default")
      (node (ref "JP2") (pin "9") (pinfunction "9_9") (pintype "passive"))
      (node (ref "U11") (pin "8") (pinfunction "1B5_8") (pintype "passive"))
    )
    (net (code "91") (name "Net-(U11-1B6)") (class "Default")
      (node (ref "JP2") (pin "11") (pinfunction "11_11") (pintype "passive"))
      (node (ref "U11") (pin "9") (pinfunction "1B6_9") (pintype "passive"))
    )
    (net (code "92") (name "Net-(U11-1B7)") (class "Default")
      (node (ref "JP2") (pin "13") (pinfunction "13_13") (pintype "passive"))
      (node (ref "U11") (pin "11") (pinfunction "1B7_11") (pintype "passive"))
    )
    (net (code "93") (name "Net-(U11-1B8)") (class "Default")
      (node (ref "JP2") (pin "15") (pinfunction "15_15") (pintype "passive"))
      (node (ref "U11") (pin "12") (pinfunction "1B8_12") (pintype "passive"))
    )
    (net (code "94") (name "Net-(U11-2B1)") (class "Default")
      (node (ref "JP4") (pin "1") (pinfunction "1_1") (pintype "passive"))
      (node (ref "U11") (pin "13") (pinfunction "2B1_13") (pintype "passive"))
    )
    (net (code "95") (name "Net-(U11-2B2)") (class "Default")
      (node (ref "JP4") (pin "3") (pinfunction "3_3") (pintype "passive"))
      (node (ref "U11") (pin "14") (pinfunction "2B2_14") (pintype "passive"))
    )
    (net (code "96") (name "Net-(U11-2B3)") (class "Default")
      (node (ref "JP4") (pin "5") (pinfunction "5_5") (pintype "passive"))
      (node (ref "U11") (pin "16") (pinfunction "2B3_16") (pintype "passive"))
    )
    (net (code "97") (name "Net-(U11-2B4)") (class "Default")
      (node (ref "JP4") (pin "7") (pinfunction "7_7") (pintype "passive"))
      (node (ref "U11") (pin "17") (pinfunction "2B4_17") (pintype "passive"))
    )
    (net (code "98") (name "Net-(U11-2B5)") (class "Default")
      (node (ref "JP4") (pin "9") (pinfunction "9_9") (pintype "passive"))
      (node (ref "U11") (pin "19") (pinfunction "2B5_19") (pintype "passive"))
    )
    (net (code "99") (name "Net-(U11-2B6)") (class "Default")
      (node (ref "JP4") (pin "11") (pinfunction "11_11") (pintype "passive"))
      (node (ref "U11") (pin "20") (pinfunction "2B6_20") (pintype "passive"))
    )
    (net (code "100") (name "Net-(U11-2B7)") (class "Default")
      (node (ref "JP4") (pin "13") (pinfunction "13_13") (pintype "passive"))
      (node (ref "U11") (pin "22") (pinfunction "2B7_22") (pintype "passive"))
    )
    (net (code "101") (name "Net-(U11-2B8)") (class "Default")
      (node (ref "JP4") (pin "15") (pinfunction "15_15") (pintype "passive"))
      (node (ref "U11") (pin "23") (pinfunction "2B8_23") (pintype "passive"))
    )
    (net (code "102") (name "Net-(U16-1B1)") (class "Default")
      (node (ref "JP5") (pin "1") (pinfunction "1_1") (pintype "passive"))
      (node (ref "U16") (pin "2") (pinfunction "1B1_2") (pintype "passive"))
    )
    (net (code "103") (name "Net-(U16-1B2)") (class "Default")
      (node (ref "JP5") (pin "3") (pinfunction "3_3") (pintype "passive"))
      (node (ref "U16") (pin "3") (pinfunction "1B2_3") (pintype "passive"))
    )
    (net (code "104") (name "Net-(U16-1B3)") (class "Default")
      (node (ref "JP5") (pin "5") (pinfunction "5_5") (pintype "passive"))
      (node (ref "U16") (pin "5") (pinfunction "1B3_5") (pintype "passive"))
    )
    (net (code "105") (name "Net-(U16-1B4)") (class "Default")
      (node (ref "JP5") (pin "7") (pinfunction "7_7") (pintype "passive"))
      (node (ref "U16") (pin "6") (pinfunction "1B4_6") (pintype "passive"))
    )
    (net (code "106") (name "Net-(U16-1B5)") (class "Default")
      (node (ref "JP5") (pin "9") (pinfunction "9_9") (pintype "passive"))
      (node (ref "U16") (pin "8") (pinfunction "1B5_8") (pintype "passive"))
    )
    (net (code "107") (name "Net-(U16-1B6)") (class "Default")
      (node (ref "JP5") (pin "11") (pinfunction "11_11") (pintype "passive"))
      (node (ref "U16") (pin "9") (pinfunction "1B6_9") (pintype "passive"))
    )
    (net (code "108") (name "Net-(U16-1B7)") (class "Default")
      (node (ref "JP5") (pin "13") (pinfunction "13_13") (pintype "passive"))
      (node (ref "U16") (pin "11") (pinfunction "1B7_11") (pintype "passive"))
    )
    (net (code "109") (name "Net-(U16-1B8)") (class "Default")
      (node (ref "JP5") (pin "15") (pinfunction "15_15") (pintype "passive"))
      (node (ref "U16") (pin "12") (pinfunction "1B8_12") (pintype "passive"))
    )
    (net (code "110") (name "Net-(U16-2B1)") (class "Default")
      (node (ref "JP7") (pin "1") (pinfunction "1_1") (pintype "passive"))
      (node (ref "U16") (pin "13") (pinfunction "2B1_13") (pintype "passive"))
    )
    (net (code "111") (name "Net-(U16-2B2)") (class "Default")
      (node (ref "JP7") (pin "3") (pinfunction "3_3") (pintype "passive"))
      (node (ref "U16") (pin "14") (pinfunction "2B2_14") (pintype "passive"))
    )
    (net (code "112") (name "Net-(U16-2B3)") (class "Default")
      (node (ref "JP7") (pin "5") (pinfunction "5_5") (pintype "passive"))
      (node (ref "U16") (pin "16") (pinfunction "2B3_16") (pintype "passive"))
    )
    (net (code "113") (name "Net-(U16-2B4)") (class "Default")
      (node (ref "JP7") (pin "7") (pinfunction "7_7") (pintype "passive"))
      (node (ref "U16") (pin "17") (pinfunction "2B4_17") (pintype "passive"))
    )
    (net (code "114") (name "Net-(U16-2B5)") (class "Default")
      (node (ref "JP7") (pin "9") (pinfunction "9_9") (pintype "passive"))
      (node (ref "U16") (pin "19") (pinfunction "2B5_19") (pintype "passive"))
    )
    (net (code "115") (name "Net-(U16-2B6)") (class "Default")
      (node (ref "JP7") (pin "11") (pinfunction "11_11") (pintype "passive"))
      (node (ref "U16") (pin "20") (pinfunction "2B6_20") (pintype "passive"))
    )
    (net (code "116") (name "Net-(U16-2B7)") (class "Default")
      (node (ref "JP7") (pin "13") (pinfunction "13_13") (pintype "passive"))
      (node (ref "U16") (pin "22") (pinfunction "2B7_22") (pintype "passive"))
    )
    (net (code "117") (name "Net-(U16-2B8)") (class "Default")
      (node (ref "JP7") (pin "15") (pinfunction "15_15") (pintype "passive"))
      (node (ref "U16") (pin "23") (pinfunction "2B8_23") (pintype "passive"))
    )
    (net (code "118") (name "Net-(U17-1B1)") (class "Default")
      (node (ref "JP6") (pin "1") (pinfunction "1_1") (pintype "passive"))
      (node (ref "U17") (pin "2") (pinfunction "1B1_2") (pintype "passive"))
    )
    (net (code "119") (name "Net-(U17-1B2)") (class "Default")
      (node (ref "JP6") (pin "3") (pinfunction "3_3") (pintype "passive"))
      (node (ref "U17") (pin "3") (pinfunction "1B2_3") (pintype "passive"))
    )
    (net (code "120") (name "Net-(U17-1B3)") (class "Default")
      (node (ref "JP6") (pin "5") (pinfunction "5_5") (pintype "passive"))
      (node (ref "U17") (pin "5") (pinfunction "1B3_5") (pintype "passive"))
    )
    (net (code "121") (name "Net-(U17-1B4)") (class "Default")
      (node (ref "JP6") (pin "7") (pinfunction "7_7") (pintype "passive"))
      (node (ref "U17") (pin "6") (pinfunction "1B4_6") (pintype "passive"))
    )
    (net (code "122") (name "Net-(U17-1B5)") (class "Default")
      (node (ref "JP6") (pin "9") (pinfunction "9_9") (pintype "passive"))
      (node (ref "U17") (pin "8") (pinfunction "1B5_8") (pintype "passive"))
    )
    (net (code "123") (name "Net-(U17-1B6)") (class "Default")
      (node (ref "JP6") (pin "11") (pinfunction "11_11") (pintype "passive"))
      (node (ref "U17") (pin "9") (pinfunction "1B6_9") (pintype "passive"))
    )
    (net (code "124") (name "Net-(U17-1B7)") (class "Default")
      (node (ref "JP6") (pin "13") (pinfunction "13_13") (pintype "passive"))
      (node (ref "U17") (pin "11") (pinfunction "1B7_11") (pintype "passive"))
    )
    (net (code "125") (name "Net-(U17-1B8)") (class "Default")
      (node (ref "JP6") (pin "15") (pinfunction "15_15") (pintype "passive"))
      (node (ref "U17") (pin "12") (pinfunction "1B8_12") (pintype "passive"))
    )
    (net (code "126") (name "Net-(U17-2B1)") (class "Default")
      (node (ref "JP8") (pin "1") (pinfunction "1_1") (pintype "passive"))
      (node (ref "U17") (pin "13") (pinfunction "2B1_13") (pintype "passive"))
    )
    (net (code "127") (name "Net-(U17-2B2)") (class "Default")
      (node (ref "JP8") (pin "3") (pinfunction "3_3") (pintype "passive"))
      (node (ref "U17") (pin "14") (pinfunction "2B2_14") (pintype "passive"))
    )
    (net (code "128") (name "Net-(U17-2B3)") (class "Default")
      (node (ref "JP8") (pin "5") (pinfunction "5_5") (pintype "passive"))
      (node (ref "U17") (pin "16") (pinfunction "2B3_16") (pintype "passive"))
    )
    (net (code "129") (name "Net-(U17-2B4)") (class "Default")
      (node (ref "JP8") (pin "7") (pinfunction "7_7") (pintype "passive"))
      (node (ref "U17") (pin "17") (pinfunction "2B4_17") (pintype "passive"))
    )
    (net (code "130") (name "Net-(U17-2B5)") (class "Default")
      (node (ref "JP8") (pin "9") (pinfunction "9_9") (pintype "passive"))
      (node (ref "U17") (pin "19") (pinfunction "2B5_19") (pintype "passive"))
    )
    (net (code "131") (name "Net-(U17-2B6)") (class "Default")
      (node (ref "JP8") (pin "11") (pinfunction "11_11") (pintype "passive"))
      (node (ref "U17") (pin "20") (pinfunction "2B6_20") (pintype "passive"))
    )
    (net (code "132") (name "Net-(U17-2B7)") (class "Default")
      (node (ref "JP8") (pin "13") (pinfunction "13_13") (pintype "passive"))
      (node (ref "U17") (pin "22") (pinfunction "2B7_22") (pintype "passive"))
    )
    (net (code "133") (name "Net-(U17-2B8)") (class "Default")
      (node (ref "JP8") (pin "15") (pinfunction "15_15") (pintype "passive"))
      (node (ref "U17") (pin "23") (pinfunction "2B8_23") (pintype "passive"))
    )
    (net (code "134") (name "unconnected-(U1B-IO_L27N_0-PadE6)") (class "Default")
      (node (ref "U1") (pin "E6") (pinfunction "IO_L27N_0_E6") (pintype "input"))
    )
    (net (code "135") (name "unconnected-(U1B-IO_L31P_0{slash}VREF_0-PadC8)") (class "Default")
      (node (ref "U1") (pin "C8") (pinfunction "IO_L31P_0/VREF_0_C8") (pintype "input"))
    )
    (net (code "136") (name "unconnected-(U1G-IO_L28P_5{slash}D7-PadM6)") (class "Default")
      (node (ref "U1") (pin "M6") (pinfunction "IO_L28P_5/D7_M6") (pintype "input"))
    )
    (net (code "137") (name "unconnected-(U1G-IO_L30P_5-PadM7)") (class "Default")
      (node (ref "U1") (pin "M7") (pinfunction "IO_L30P_5_M7") (pintype "input"))
    )
    (net (code "138") (name "unconnected-(U1G-IO_L32P_5{slash}GCLK2-PadN8)") (class "Default")
      (node (ref "U1") (pin "N8") (pinfunction "IO_L32P_5/GCLK2_N8") (pintype "input"))
    )
    (net (code "139") (name "unconnected-(U1G-IO{slash}VREF_5-PadT8)") (class "Default")
      (node (ref "U1") (pin "T8") (pinfunction "IO/VREF_5_T8") (pintype "input"))
    )
    (net (code "140") (name "unconnected-(U1H-IO_L19N_6-PadM4)") (class "Default")
      (node (ref "U1") (pin "M4") (pinfunction "IO_L19N_6_M4") (pintype "input"))
    )
    (net (code "141") (name "unconnected-(U1H-IO_L21N_6-PadL5)") (class "Default")
      (node (ref "U1") (pin "L5") (pinfunction "IO_L21N_6_L5") (pintype "input"))
    )
    (net (code "142") (name "unconnected-(U1H-IO_L21P_6-PadL4)") (class "Default")
      (node (ref "U1") (pin "L4") (pinfunction "IO_L21P_6_L4") (pintype "input"))
    )
    (net (code "143") (name "unconnected-(U1H-IO_L23N_6-PadK5)") (class "Default")
      (node (ref "U1") (pin "K5") (pinfunction "IO_L23N_6_K5") (pintype "input"))
    )
    (net (code "144") (name "unconnected-(U1H-IO_L23P_6-PadK4)") (class "Default")
      (node (ref "U1") (pin "K4") (pinfunction "IO_L23P_6_K4") (pintype "input"))
    )
    (net (code "145") (name "unconnected-(U1H-IO_L39N_6-PadJ4)") (class "Default")
      (node (ref "U1") (pin "J4") (pinfunction "IO_L39N_6_J4") (pintype "input"))
    )
    (net (code "146") (name "unconnected-(U1H-IO_L39P_6-PadJ3)") (class "Default")
      (node (ref "U1") (pin "J3") (pinfunction "IO_L39P_6_J3") (pintype "input"))
    )
    (net (code "147") (name "unconnected-(U1I-IO_L16P_7{slash}VREF_7-PadC3)") (class "Default")
      (node (ref "U1") (pin "C3") (pinfunction "IO_L16P_7/VREF_7_C3") (pintype "input"))
    )
    (net (code "148") (name "unconnected-(U1I-IO_L19N_7{slash}VREF_7-PadE3)") (class "Default")
      (node (ref "U1") (pin "E3") (pinfunction "IO_L19N_7/VREF_7_E3") (pintype "input"))
    )
    (net (code "149") (name "unconnected-(U1I-IO_L21P_7-PadE4)") (class "Default")
      (node (ref "U1") (pin "E4") (pinfunction "IO_L21P_7_E4") (pintype "input"))
    )
    (net (code "150") (name "unconnected-(U1I-IO_L23N_7-PadG5)") (class "Default")
      (node (ref "U1") (pin "G5") (pinfunction "IO_L23N_7_G5") (pintype "input"))
    )
    (net (code "151") (name "unconnected-(U1I-IO_L23P_7-PadF5)") (class "Default")
      (node (ref "U1") (pin "F5") (pinfunction "IO_L23P_7_F5") (pintype "input"))
    )
    (net (code "152") (name "unconnected-(U1I-IO_L39N_7-PadH3)") (class "Default")
      (node (ref "U1") (pin "H3") (pinfunction "IO_L39N_7_H3") (pintype "input"))
    )
    (net (code "153") (name "unconnected-(U1I-IO_L39P_7-PadH4)") (class "Default")
      (node (ref "U1") (pin "H4") (pinfunction "IO_L39P_7_H4") (pintype "input"))
    )
  )
)
